# MAIN.net
KiCad netlist of a schematic drawn in Altium Designer
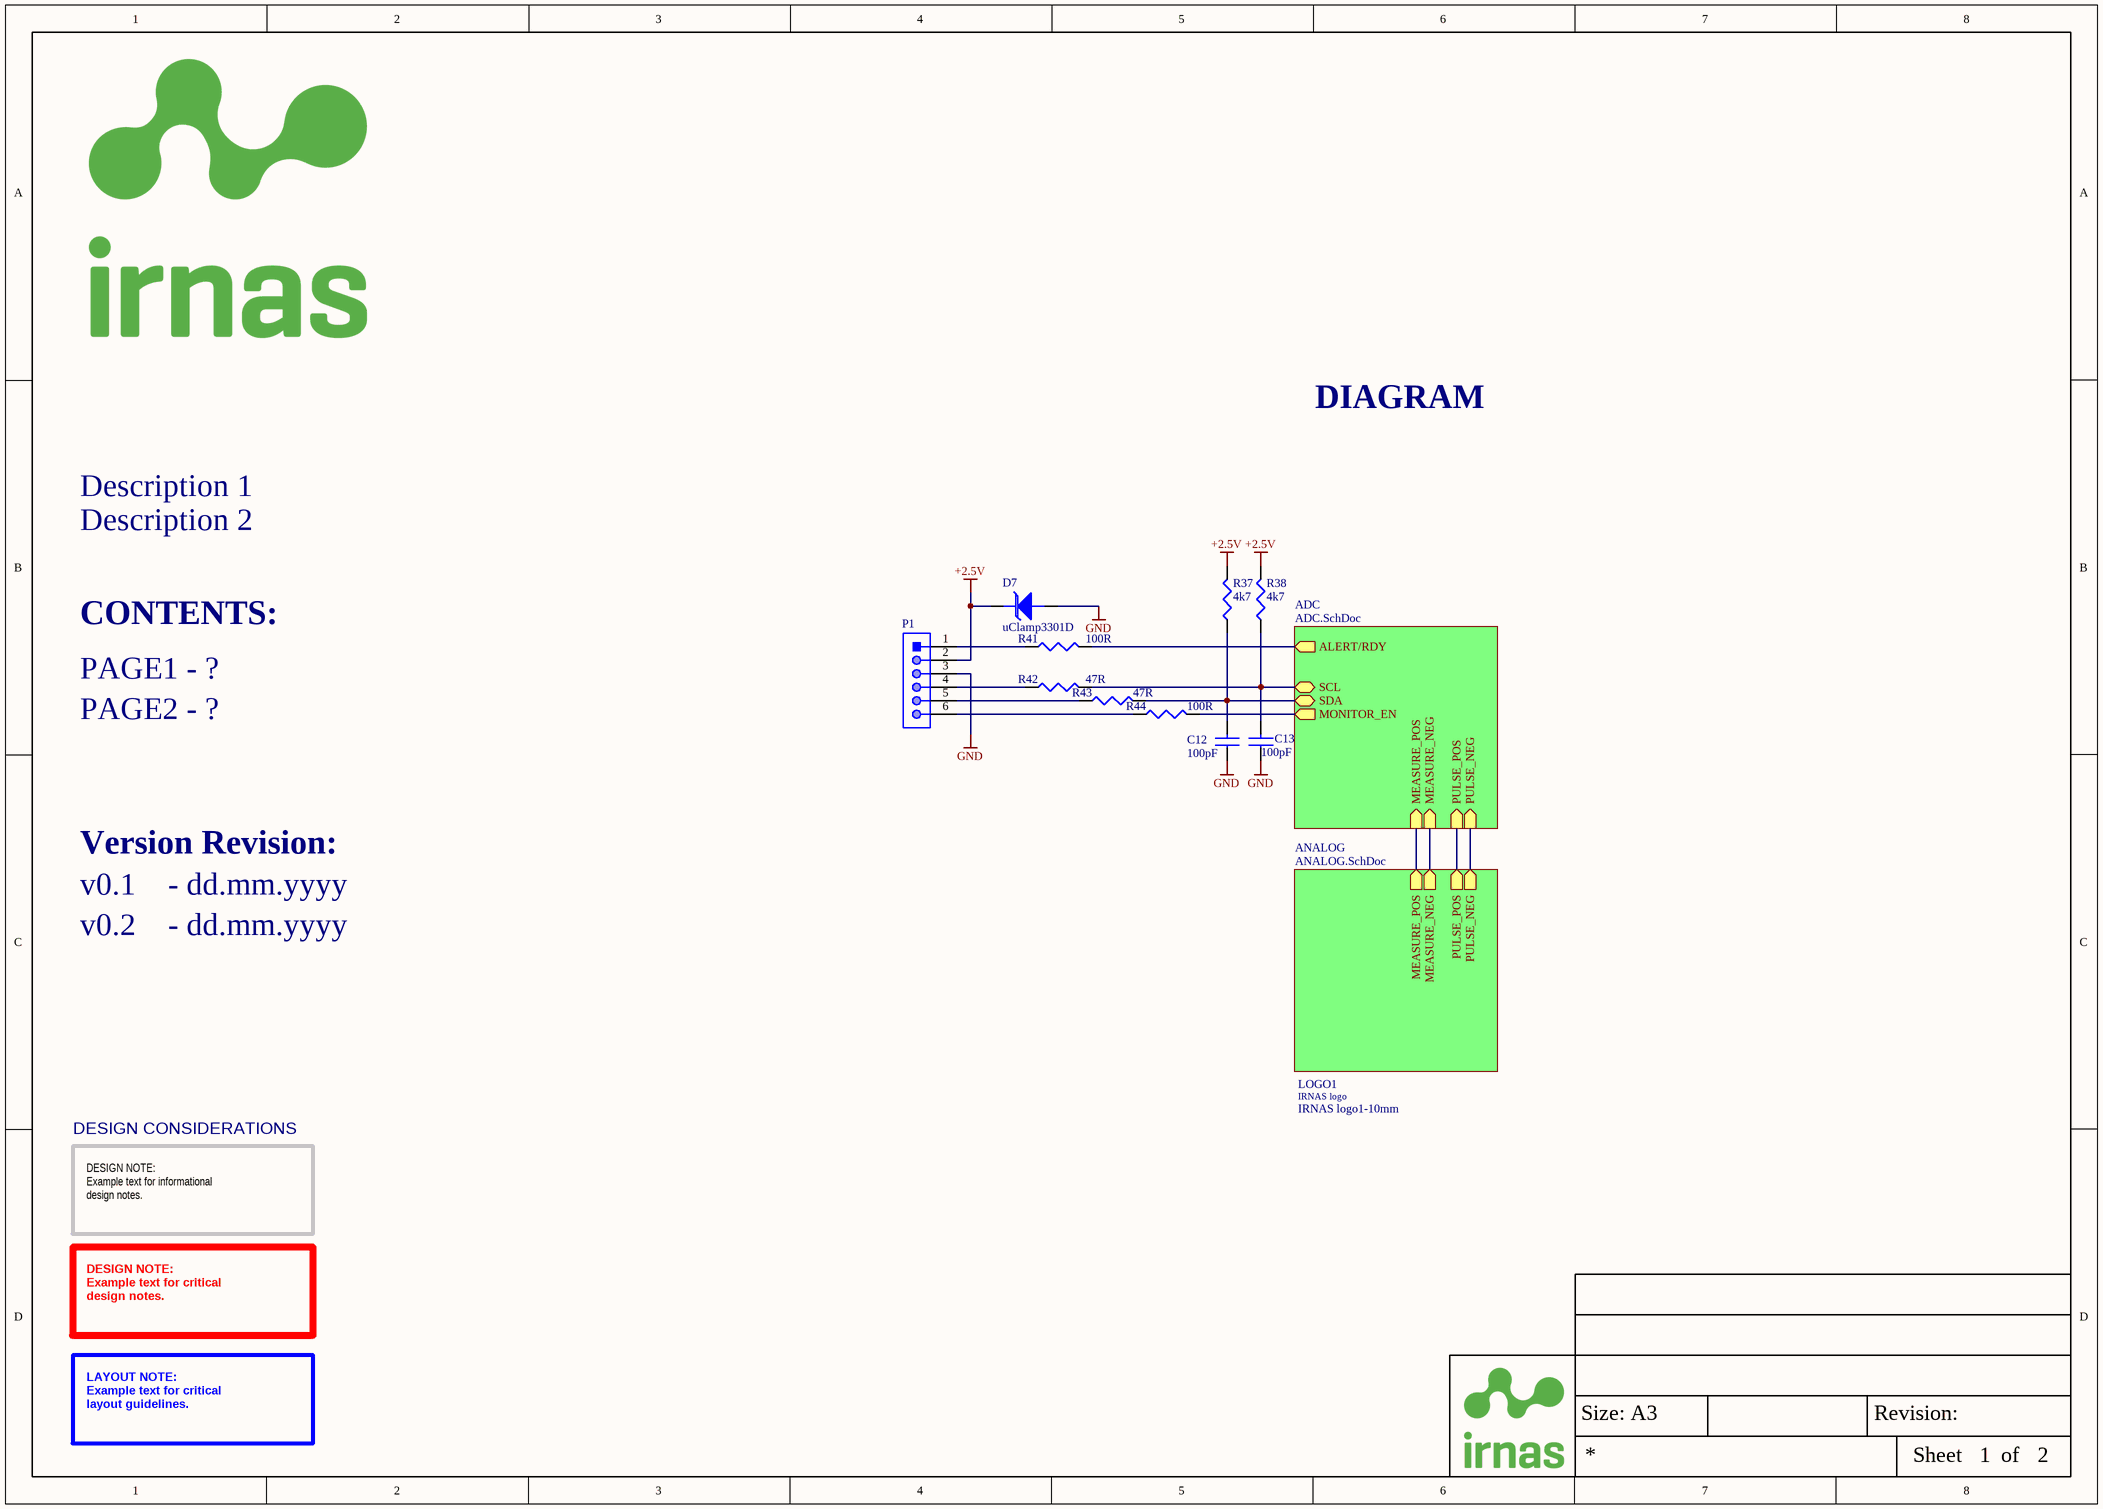
[diagram p0: MAIN.SchDoc]

(export (version "E")
  (design (tool "Eeschema 10.0.6"))
  (components
    (comp (ref "C12")
      (value "100pF")
      (footprint "CAP0402")
      (description "Cap Ceramic 100pF 50V X7R 10% SMD 0402 125C T/R")
      (fields
        (field (name "MANUFACTURER") "KEMET")
        (field (name "MANUFACTURER PART NUMBER") "C0402C101K5RACTU")
      )
      (libsource (lib "Passive") (part "C - 100pF/0402"))
    )
    (comp (ref "C13")
      (value "100pF")
      (footprint "CAP0402")
      (description "Cap Ceramic 100pF 50V X7R 10% SMD 0402 125C T/R")
      (fields
        (field (name "MANUFACTURER") "KEMET")
        (field (name "MANUFACTURER PART NUMBER") "C0402C101K5RACTU")
      )
      (libsource (lib "Passive") (part "C - 100pF/0402"))
    )
    (comp (ref "D7")
      (value "uClamp3301D")
      (footprint "SOD-323")
      (description "TVS Diode, µClamp Series, Unidirectional, 3.3 V, 9.5 V")
      (fields
        (field (name "MANUFACTURER") "DIODES INC.")
        (field (name "MANUFACTURER PART NUMBER") "1N4148W-7-F.")
      )
      (libsource (lib "Active") (part "D_TVS - uClamp3301D"))
    )
    (comp (ref "LOGO1")
      (value "IRNAS logo1-10mm")
      (footprint "LOGO_1-10MM")
      (libsource (lib "Graphical") (part "IRNAS logo1-10mm"))
    )
    (comp (ref "P1")
      (value "IRNAS - LION_EXTENSION")
      (footprint "IRNAL_LION_ADDON")
      (description "LION_EXTENSION")
      (libsource (lib "Connectors") (part "IRNAS - LION_EXTENSION"))
    )
    (comp (ref "R37")
      (value "4k7")
      (footprint "RES0402")
      (description "4.7 kohm, MCWR Series, 50 V")
      (fields
        (field (name "MANUFACTURER") "MULTICOMP")
        (field (name "MANUFACTURER PART NUMBER") "MCMR06X4701FTL")
      )
      (libsource (lib "Passive") (part "R - 4k7/0402"))
    )
    (comp (ref "R38")
      (value "4k7")
      (footprint "RES0402")
      (description "4.7 kohm, MCWR Series, 50 V")
      (fields
        (field (name "MANUFACTURER") "MULTICOMP")
        (field (name "MANUFACTURER PART NUMBER") "MCMR06X4701FTL")
      )
      (libsource (lib "Passive") (part "R - 4k7/0402"))
    )
    (comp (ref "R41")
      (value "100R")
      (footprint "RES0402")
      (fields
        (field (name "MANUFACTURER") "Multicomp")
        (field (name "MANUFACTURER PART NUMBER") "MCMR04X1000FTL")
        (field (name "TOLERANCE") "1%")
      )
      (libsource (lib "Passive") (part "R - 100R/0402"))
    )
    (comp (ref "R42")
      (value "47R")
      (footprint "RES0402")
      (description "MULTICOMP - MCMR06X4702FTL - RES, CERAMIC, 47R, 1%, 0.1W, 0402")
      (fields
        (field (name "MANUFACTURER") "MULTICOMP")
        (field (name "MANUFACTURER PART NUMBER") "MCMR06X4702FTL")
      )
      (libsource (lib "Passive") (part "R - 47R/0402"))
    )
    (comp (ref "R43")
      (value "47R")
      (footprint "RES0402")
      (description "MULTICOMP - MCMR06X4702FTL - RES, CERAMIC, 47R, 1%, 0.1W, 0402")
      (fields
        (field (name "MANUFACTURER") "MULTICOMP")
        (field (name "MANUFACTURER PART NUMBER") "MCMR06X4702FTL")
      )
      (libsource (lib "Passive") (part "R - 47R/0402"))
    )
    (comp (ref "R44")
      (value "100R")
      (footprint "RES0402")
      (fields
        (field (name "MANUFACTURER") "Multicomp")
        (field (name "MANUFACTURER PART NUMBER") "MCMR04X1000FTL")
        (field (name "TOLERANCE") "1%")
      )
      (libsource (lib "Passive") (part "R - 100R/0402"))
    )
  )
  (nets
    (net (code "1") (name "+2.5V") (class "Default")
      (node (ref "D7") (pin "K") (pinfunction "cathode_K") (pintype "passive"))
      (node (ref "P1") (pin "2") (pinfunction "2_2") (pintype "passive"))
      (node (ref "R37") (pin "2") (pinfunction "2_2") (pintype "passive"))
      (node (ref "R38") (pin "2") (pinfunction "2_2") (pintype "passive"))
    )
    (net (code "2") (name "/ALERT{slash}RDY") (class "Default")
      (node (ref "R41") (pin "2") (pinfunction "2_2") (pintype "passive"))
    )
    (net (code "5") (name "/MONITOR_EN") (class "Default")
      (node (ref "R44") (pin "2") (pinfunction "2_2") (pintype "passive"))
    )
    (net (code "8") (name "/SCL") (class "Default")
      (node (ref "C13") (pin "2") (pinfunction "2_2") (pintype "passive"))
      (node (ref "R38") (pin "1") (pinfunction "1_1") (pintype "passive"))
      (node (ref "R42") (pin "2") (pinfunction "2_2") (pintype "passive"))
    )
    (net (code "9") (name "/SDA") (class "Default")
      (node (ref "C12") (pin "2") (pinfunction "2_2") (pintype "passive"))
      (node (ref "R37") (pin "1") (pinfunction "1_1") (pintype "passive"))
      (node (ref "R43") (pin "2") (pinfunction "2_2") (pintype "passive"))
    )
    (net (code "10") (name "GND") (class "Default")
      (node (ref "C12") (pin "1") (pinfunction "1_1") (pintype "passive"))
      (node (ref "C13") (pin "1") (pinfunction "1_1") (pintype "passive"))
      (node (ref "D7") (pin "A") (pinfunction "ANODE_A") (pintype "passive"))
      (node (ref "P1") (pin "3") (pinfunction "3_3") (pintype "passive"))
    )
    (net (code "11") (name "Net-(P1-Pad1)") (class "Default")
      (node (ref "P1") (pin "1") (pinfunction "1_1") (pintype "passive"))
      (node (ref "R41") (pin "1") (pinfunction "1_1") (pintype "passive"))
    )
    (net (code "12") (name "Net-(P1-Pad4)") (class "Default")
      (node (ref "P1") (pin "4") (pinfunction "4_4") (pintype "passive"))
      (node (ref "R42") (pin "1") (pinfunction "1_1") (pintype "passive"))
    )
    (net (code "13") (name "Net-(P1-Pad5)") (class "Default")
      (node (ref "P1") (pin "5") (pinfunction "5_5") (pintype "passive"))
      (node (ref "R43") (pin "1") (pinfunction "1_1") (pintype "passive"))
    )
    (net (code "14") (name "Net-(P1-Pad6)") (class "Default")
      (node (ref "P1") (pin "6") (pinfunction "6_6") (pintype "passive"))
      (node (ref "R44") (pin "1") (pinfunction "1_1") (pintype "passive"))
    )
  )
)
